# MIPI-DSI.net
KiCad netlist of a schematic drawn in Altium Designer
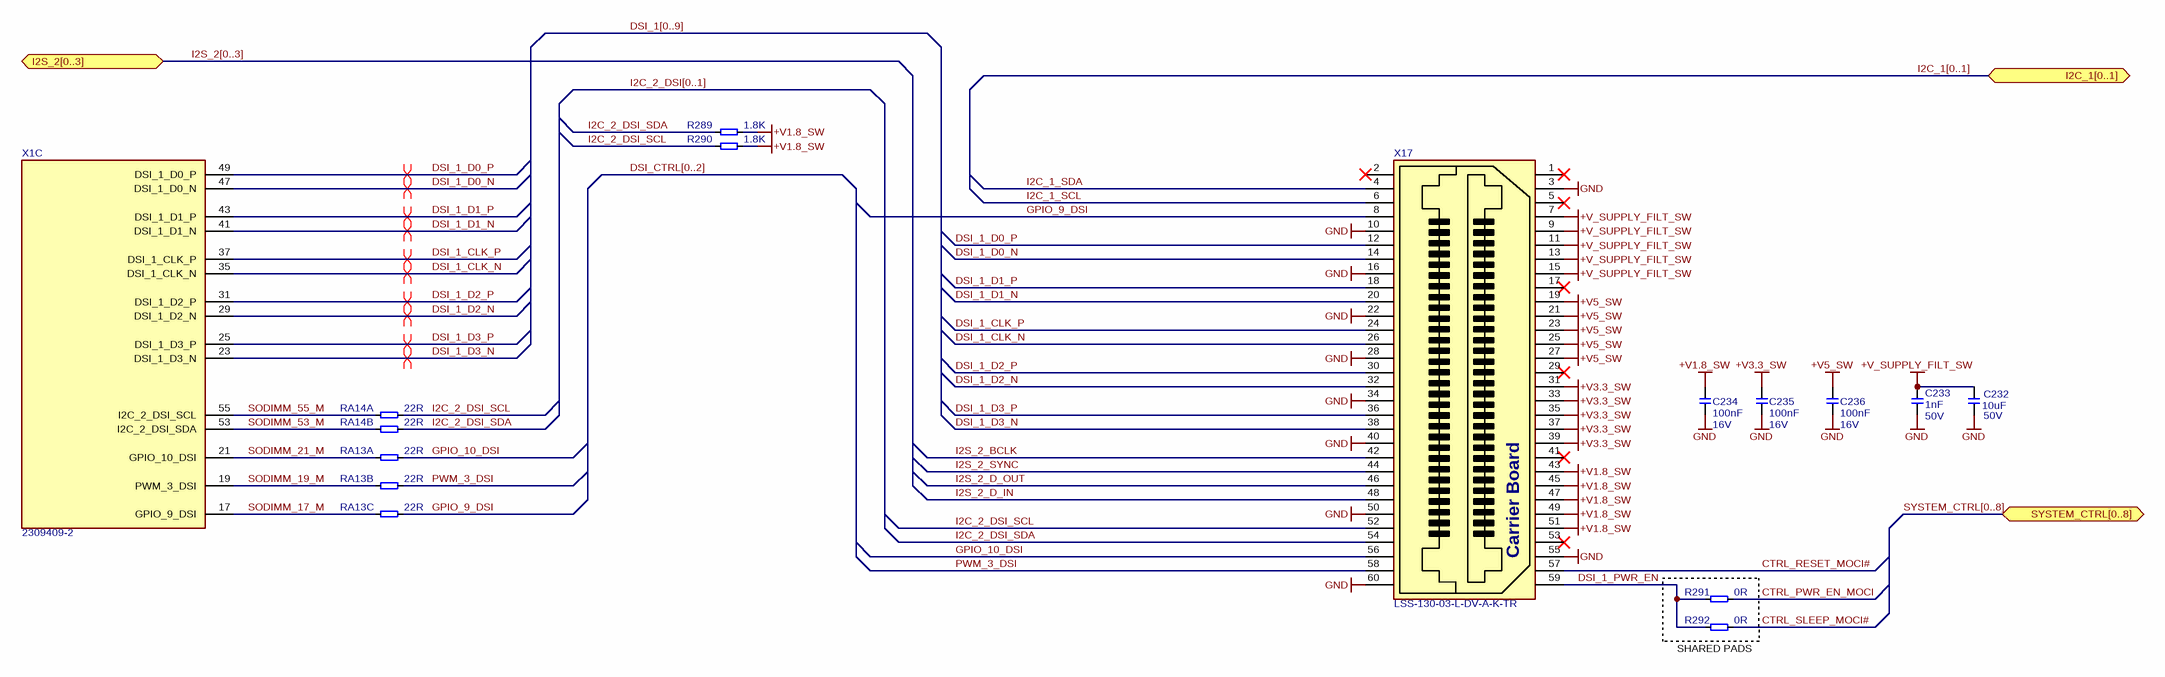
[diagram p0: MIPI-DSI.SchDoc]

(export (version "E")
  (design (tool "Eeschema 10.0.6"))
  (components
    (comp (ref "C232")
      (value "10uF")
      (footprint "T_CAPC1206X60N")
      (description "Capacitor Ceramic X5R 10uF 50V 20% 1206")
      (fields (field (name "TOLERANCE") "20%") (field (name "RATING") "50V"))
      (libsource (lib "Dahlia Carrier Board") (part "C-X5R-10uF-50V-20%-1206"))
    )
    (comp (ref "C233")
      (value "1nF")
      (footprint "CAPC1005X60N")
      (description "Capacitor Ceramic X7R 1nF 50V 10% 0402")
      (fields (field (name "TOLERANCE") "10%") (field (name "RATING") "50V"))
      (libsource (lib "Dahlia Carrier Board") (part "C-X7R-1nF-50V-10%-0402"))
    )
    (comp (ref "C234")
      (value "100nF")
      (footprint "CAPC1005X60N")
      (description "Capacitor Ceramic X7R 100nF 16V 10% 0402")
      (fields (field (name "TOLERANCE") "10%") (field (name "RATING") "16V"))
      (libsource (lib "Dahlia Carrier Board") (part "C-X7R-100nF-16V-10%-0402"))
    )
    (comp (ref "C235")
      (value "100nF")
      (footprint "CAPC1005X60N")
      (description "Capacitor Ceramic X7R 100nF 16V 10% 0402")
      (fields (field (name "TOLERANCE") "10%") (field (name "RATING") "16V"))
      (libsource (lib "Dahlia Carrier Board") (part "C-X7R-100nF-16V-10%-0402"))
    )
    (comp (ref "C236")
      (value "100nF")
      (footprint "CAPC1005X60N")
      (description "Capacitor Ceramic X7R 100nF 16V 10% 0402")
      (fields (field (name "TOLERANCE") "10%") (field (name "RATING") "16V"))
      (libsource (lib "Dahlia Carrier Board") (part "C-X7R-100nF-16V-10%-0402"))
    )
    (comp (ref "R289")
      (value "1.8K")
      (footprint "RESC1005X40N")
      (description "Resistor 1.8 Kohm 63mW 5% 0402")
      (fields (field (name "TOLERANCE") "5%"))
      (libsource (lib "Dahlia Carrier Board") (part "R-1.8K-63mW-5%-0402"))
    )
    (comp (ref "R290")
      (value "1.8K")
      (footprint "RESC1005X40N")
      (description "Resistor 1.8 Kohm 63mW 5% 0402")
      (fields (field (name "TOLERANCE") "5%"))
      (libsource (lib "Dahlia Carrier Board") (part "R-1.8K-63mW-5%-0402"))
    )
    (comp (ref "R291")
      (value "0R")
      (footprint "T_RESC0603X30N")
      (description "Resistor 0 ohm 63mW 1% 0603")
      (fields (field (name "TOLERANCE") "1%"))
      (libsource (lib "Dahlia Carrier Board") (part "R-0R-63mW-1%-0603"))
    )
    (comp (ref "R292")
      (value "0R")
      (footprint "T_RESC0603X30N")
      (description "Resistor 0 ohm 63mW 1% 0603")
      (fields (field (name "TOLERANCE") "1%"))
      (libsource (lib "Dahlia Carrier Board") (part "R-0R-63mW-1%-0603"))
    )
    (comp (ref "RA13")
      (value "22R")
      (footprint "T_Resistor_Array_X4")
      (description "Resistor Array 22 R 63mW 5% 1206")
      (fields (field (name "TOLERANCE") "5%"))
      (libsource (lib "Dahlia Carrier Board") (part "RA-22R-63mW-5%-1206-div"))
    )
    (comp (ref "RA14")
      (value "22R")
      (footprint "T_Resistor_Array_X4")
      (description "Resistor Array 22 R 63mW 5% 1206")
      (fields (field (name "TOLERANCE") "5%"))
      (libsource (lib "Dahlia Carrier Board") (part "RA-22R-63mW-5%-1206-div"))
    )
    (comp (ref "X1")
      (value "2309409-2")
      (footprint "CON-TE-2309409-2-SOLDERABLE-STANDOFFS")
      (description "DDR4 SODIMM Socket, 260 pins, 5.2mm(H), 0.5mm Pitch")
      (libsource (lib "Dahlia Carrier Board") (part "CON-TE-2309409-2"))
    )
    (comp (ref "X17")
      (value "LSS-130-03-L-DV-A-K-TR")
      (footprint "CON-SAMTEC-LSS-130-03-L-DV-A-CARRIER")
      (description "60 Position Connector, Self Mating, Non-Gendered, Surface Mount")
      (fields (field (name "MANUFACTURER PART NO.") "LSS-130-03-L-DV-A-K-TR"))
      (libsource (lib "Dahlia Carrier Board") (part "CON-Samtec-LSS-130-03-L-DV-A-K-TR-CARRIER"))
    )
  )
  (nets
    (net (code "31") (name "+V1.8_SW") (class "Default")
      (node (ref "C234") (pin "2") (pinfunction "2_2") (pintype "passive"))
      (node (ref "R289") (pin "1") (pinfunction "1_1") (pintype "passive"))
      (node (ref "R290") (pin "1") (pinfunction "1_1") (pintype "passive"))
      (node (ref "X17") (pin "43") (pinfunction "43_43") (pintype "passive"))
      (node (ref "X17") (pin "45") (pinfunction "45_45") (pintype "passive"))
      (node (ref "X17") (pin "47") (pinfunction "47_47") (pintype "passive"))
      (node (ref "X17") (pin "49") (pinfunction "49_49") (pintype "passive"))
      (node (ref "X17") (pin "51") (pinfunction "51_51") (pintype "passive"))
    )
    (net (code "32") (name "+V3.3_SW") (class "Default")
      (node (ref "C235") (pin "2") (pinfunction "2_2") (pintype "passive"))
      (node (ref "X17") (pin "31") (pinfunction "31_31") (pintype "passive"))
      (node (ref "X17") (pin "33") (pinfunction "33_33") (pintype "passive"))
      (node (ref "X17") (pin "35") (pinfunction "35_35") (pintype "passive"))
      (node (ref "X17") (pin "37") (pinfunction "37_37") (pintype "passive"))
      (node (ref "X17") (pin "39") (pinfunction "39_39") (pintype "passive"))
    )
    (net (code "33") (name "+V5_SW") (class "Default")
      (node (ref "C236") (pin "2") (pinfunction "2_2") (pintype "passive"))
      (node (ref "X17") (pin "19") (pinfunction "19_19") (pintype "passive"))
      (node (ref "X17") (pin "21") (pinfunction "21_21") (pintype "passive"))
      (node (ref "X17") (pin "23") (pinfunction "23_23") (pintype "passive"))
      (node (ref "X17") (pin "25") (pinfunction "25_25") (pintype "passive"))
      (node (ref "X17") (pin "27") (pinfunction "27_27") (pintype "passive"))
    )
    (net (code "34") (name "+V_SUPPLY_FILT_SW") (class "Default")
      (node (ref "C232") (pin "2") (pinfunction "2_2") (pintype "passive"))
      (node (ref "C233") (pin "2") (pinfunction "2_2") (pintype "passive"))
      (node (ref "X17") (pin "11") (pinfunction "11_11") (pintype "passive"))
      (node (ref "X17") (pin "13") (pinfunction "13_13") (pintype "passive"))
      (node (ref "X17") (pin "15") (pinfunction "15_15") (pintype "passive"))
      (node (ref "X17") (pin "7") (pinfunction "7_7") (pintype "passive"))
      (node (ref "X17") (pin "9") (pinfunction "9_9") (pintype "passive"))
    )
    (net (code "35") (name "/CTRL_PWR_EN_MOCI") (class "Default")
      (node (ref "R291") (pin "2") (pinfunction "2_2") (pintype "passive"))
    )
    (net (code "36") (name "/CTRL_RESET_MOCI#") (class "Default")
      (node (ref "X17") (pin "57") (pinfunction "57_57") (pintype "passive"))
    )
    (net (code "37") (name "/CTRL_SLEEP_MOCI#") (class "Default")
      (node (ref "R292") (pin "2") (pinfunction "2_2") (pintype "passive"))
    )
    (net (code "39") (name "/DSI_1_CLK_N") (class "Default")
      (node (ref "X1") (pin "35") (pinfunction "DSI_1_CLK_N_35") (pintype "passive"))
      (node (ref "X17") (pin "26") (pinfunction "26_26") (pintype "passive"))
    )
    (net (code "40") (name "/DSI_1_CLK_P") (class "Default")
      (node (ref "X1") (pin "37") (pinfunction "DSI_1_CLK_P_37") (pintype "passive"))
      (node (ref "X17") (pin "24") (pinfunction "24_24") (pintype "passive"))
    )
    (net (code "41") (name "/DSI_1_D0_N") (class "Default")
      (node (ref "X1") (pin "47") (pinfunction "DSI_1_D0_N_47") (pintype "passive"))
      (node (ref "X17") (pin "14") (pinfunction "14_14") (pintype "passive"))
    )
    (net (code "42") (name "/DSI_1_D0_P") (class "Default")
      (node (ref "X1") (pin "49") (pinfunction "DSI_1_D0_P_49") (pintype "passive"))
      (node (ref "X17") (pin "12") (pinfunction "12_12") (pintype "passive"))
    )
    (net (code "43") (name "/DSI_1_D1_N") (class "Default")
      (node (ref "X1") (pin "41") (pinfunction "DSI_1_D1_N_41") (pintype "passive"))
      (node (ref "X17") (pin "20") (pinfunction "20_20") (pintype "passive"))
    )
    (net (code "44") (name "/DSI_1_D1_P") (class "Default")
      (node (ref "X1") (pin "43") (pinfunction "DSI_1_D1_P_43") (pintype "passive"))
      (node (ref "X17") (pin "18") (pinfunction "18_18") (pintype "passive"))
    )
    (net (code "45") (name "/DSI_1_D2_N") (class "Default")
      (node (ref "X1") (pin "29") (pinfunction "DSI_1_D2_N_29") (pintype "passive"))
      (node (ref "X17") (pin "32") (pinfunction "32_32") (pintype "passive"))
    )
    (net (code "46") (name "/DSI_1_D2_P") (class "Default")
      (node (ref "X1") (pin "31") (pinfunction "DSI_1_D2_P_31") (pintype "passive"))
      (node (ref "X17") (pin "30") (pinfunction "30_30") (pintype "passive"))
    )
    (net (code "47") (name "/DSI_1_D3_N") (class "Default")
      (node (ref "X1") (pin "23") (pinfunction "DSI_1_D3_N_23") (pintype "passive"))
      (node (ref "X17") (pin "38") (pinfunction "38_38") (pintype "passive"))
    )
    (net (code "48") (name "/DSI_1_D3_P") (class "Default")
      (node (ref "X1") (pin "25") (pinfunction "DSI_1_D3_P_25") (pintype "passive"))
      (node (ref "X17") (pin "36") (pinfunction "36_36") (pintype "passive"))
    )
    (net (code "49") (name "/DSI_1_PWR_EN") (class "Default")
      (node (ref "R291") (pin "1") (pinfunction "1_1") (pintype "passive"))
      (node (ref "R292") (pin "1") (pinfunction "1_1") (pintype "passive"))
      (node (ref "X17") (pin "59") (pinfunction "59_59") (pintype "passive"))
    )
    (net (code "51") (name "/GPIO_9_DSI") (class "Default")
      (node (ref "RA13") (pin "7") (pinfunction "7_7") (pintype "passive"))
      (node (ref "X17") (pin "8") (pinfunction "8_8") (pintype "passive"))
    )
    (net (code "52") (name "/GPIO_10_DSI") (class "Default")
      (node (ref "RA13") (pin "5") (pinfunction "5_5") (pintype "passive"))
      (node (ref "X17") (pin "56") (pinfunction "56_56") (pintype "passive"))
    )
    (net (code "54") (name "/I2C_1_SCL") (class "Default")
      (node (ref "X17") (pin "6") (pinfunction "6_6") (pintype "passive"))
    )
    (net (code "55") (name "/I2C_1_SDA") (class "Default")
      (node (ref "X17") (pin "4") (pinfunction "4_4") (pintype "passive"))
    )
    (net (code "57") (name "/I2C_2_DSI_SCL") (class "Default")
      (node (ref "R290") (pin "2") (pinfunction "2_2") (pintype "passive"))
      (node (ref "RA14") (pin "5") (pinfunction "5_5") (pintype "passive"))
      (node (ref "X17") (pin "52") (pinfunction "52_52") (pintype "passive"))
    )
    (net (code "58") (name "/I2C_2_DSI_SDA") (class "Default")
      (node (ref "R289") (pin "2") (pinfunction "2_2") (pintype "passive"))
      (node (ref "RA14") (pin "6") (pinfunction "6_6") (pintype "passive"))
      (node (ref "X17") (pin "54") (pinfunction "54_54") (pintype "passive"))
    )
    (net (code "60") (name "/I2S_2_BCLK") (class "Default")
      (node (ref "X17") (pin "42") (pinfunction "42_42") (pintype "passive"))
    )
    (net (code "61") (name "/I2S_2_D_IN") (class "Default")
      (node (ref "X17") (pin "48") (pinfunction "48_48") (pintype "passive"))
    )
    (net (code "62") (name "/I2S_2_D_OUT") (class "Default")
      (node (ref "X17") (pin "46") (pinfunction "46_46") (pintype "passive"))
    )
    (net (code "63") (name "/I2S_2_SYNC") (class "Default")
      (node (ref "X17") (pin "44") (pinfunction "44_44") (pintype "passive"))
    )
    (net (code "64") (name "/PWM_3_DSI") (class "Default")
      (node (ref "RA13") (pin "6") (pinfunction "6_6") (pintype "passive"))
      (node (ref "X17") (pin "58") (pinfunction "58_58") (pintype "passive"))
    )
    (net (code "65") (name "/SODIMM_17_M") (class "Default")
      (node (ref "RA13") (pin "3") (pinfunction "3_3") (pintype "passive"))
      (node (ref "X1") (pin "17") (pinfunction "GPIO_9_DSI_17") (pintype "passive"))
    )
    (net (code "66") (name "/SODIMM_19_M") (class "Default")
      (node (ref "RA13") (pin "2") (pinfunction "2_2") (pintype "passive"))
      (node (ref "X1") (pin "19") (pinfunction "PWM_3_DSI_19") (pintype "passive"))
    )
    (net (code "67") (name "/SODIMM_21_M") (class "Default")
      (node (ref "RA13") (pin "1") (pinfunction "1_1") (pintype "passive"))
      (node (ref "X1") (pin "21") (pinfunction "GPIO_10_DSI_21") (pintype "passive"))
    )
    (net (code "68") (name "/SODIMM_53_M") (class "Default")
      (node (ref "RA14") (pin "2") (pinfunction "2_2") (pintype "passive"))
      (node (ref "X1") (pin "53") (pinfunction "I2C_2_DSI_SDA_53") (pintype "passive"))
    )
    (net (code "69") (name "/SODIMM_55_M") (class "Default")
      (node (ref "RA14") (pin "1") (pinfunction "1_1") (pintype "passive"))
      (node (ref "X1") (pin "55") (pinfunction "I2C_2_DSI_SCL_55") (pintype "passive"))
    )
    (net (code "71") (name "GND") (class "Default")
      (node (ref "C232") (pin "1") (pinfunction "1_1") (pintype "passive"))
      (node (ref "C233") (pin "1") (pinfunction "1_1") (pintype "passive"))
      (node (ref "C234") (pin "1") (pinfunction "1_1") (pintype "passive"))
      (node (ref "C235") (pin "1") (pinfunction "1_1") (pintype "passive"))
      (node (ref "C236") (pin "1") (pinfunction "1_1") (pintype "passive"))
      (node (ref "X17") (pin "10") (pinfunction "10_10") (pintype "passive"))
      (node (ref "X17") (pin "16") (pinfunction "16_16") (pintype "passive"))
      (node (ref "X17") (pin "22") (pinfunction "22_22") (pintype "passive"))
      (node (ref "X17") (pin "28") (pinfunction "28_28") (pintype "passive"))
      (node (ref "X17") (pin "3") (pinfunction "3_3") (pintype "passive"))
      (node (ref "X17") (pin "34") (pinfunction "34_34") (pintype "passive"))
      (node (ref "X17") (pin "40") (pinfunction "40_40") (pintype "passive"))
      (node (ref "X17") (pin "50") (pinfunction "50_50") (pintype "passive"))
      (node (ref "X17") (pin "55") (pinfunction "55_55") (pintype "passive"))
      (node (ref "X17") (pin "60") (pinfunction "60_60") (pintype "passive"))
    )
    (net (code "72") (name "unconnected-(X17-Pad1)") (class "Default")
      (node (ref "X17") (pin "1") (pinfunction "1_1") (pintype "passive+no_connect"))
    )
    (net (code "73") (name "unconnected-(X17-Pad2)") (class "Default")
      (node (ref "X17") (pin "2") (pinfunction "2_2") (pintype "passive+no_connect"))
    )
    (net (code "74") (name "unconnected-(X17-Pad5)") (class "Default")
      (node (ref "X17") (pin "5") (pinfunction "5_5") (pintype "passive+no_connect"))
    )
    (net (code "75") (name "unconnected-(X17-Pad17)") (class "Default")
      (node (ref "X17") (pin "17") (pinfunction "17_17") (pintype "passive+no_connect"))
    )
    (net (code "76") (name "unconnected-(X17-Pad29)") (class "Default")
      (node (ref "X17") (pin "29") (pinfunction "29_29") (pintype "passive+no_connect"))
    )
    (net (code "77") (name "unconnected-(X17-Pad41)") (class "Default")
      (node (ref "X17") (pin "41") (pinfunction "41_41") (pintype "passive+no_connect"))
    )
    (net (code "78") (name "unconnected-(X17-Pad53)") (class "Default")
      (node (ref "X17") (pin "53") (pinfunction "53_53") (pintype "passive+no_connect"))
    )
  )
)
